# MicroMod-Artemis-ProcessorBoard.net
KiCad netlist of a schematic drawn in EAGLE
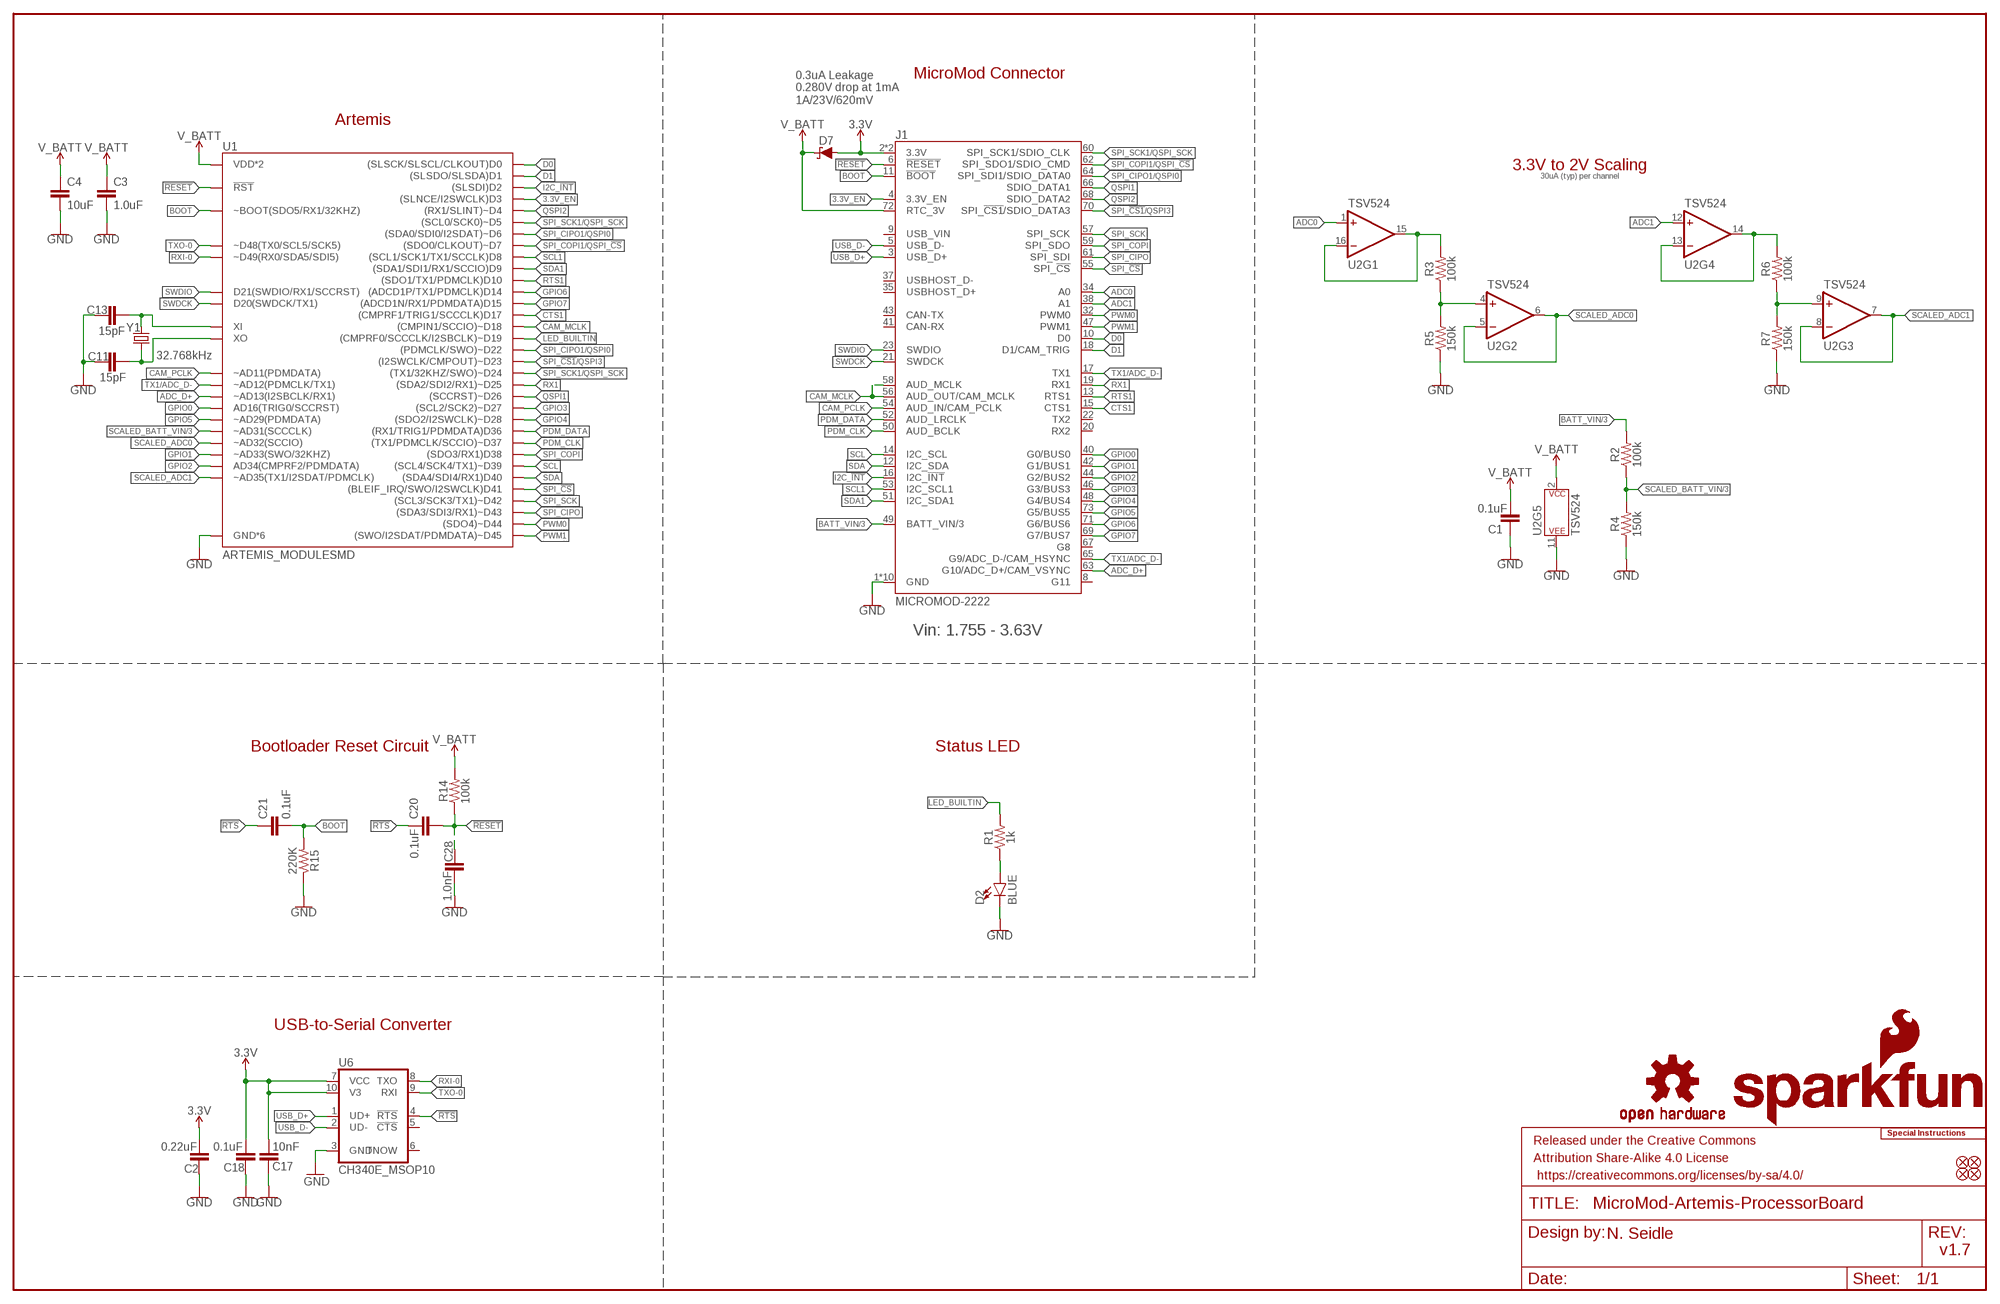
[diagram p0: schematic, sheet 1]

(export (version "E")
  (design (tool "Eeschema 10.0.6"))
  (components
    (comp (ref "C1")
      (value "0.1uF")
      (footprint "eagle-import:0402-TIGHT")
      (libsource (lib "eagle-import") (part "0.1UF-0402T-16V-10%"))
    )
    (comp (ref "C2")
      (value "0.22uF")
      (footprint "eagle-import:0402-TIGHT")
      (libsource (lib "eagle-import") (part "0.22UF-0402T-10V-10%"))
    )
    (comp (ref "C3")
      (value "1.0uF")
      (footprint "eagle-import:0402-TIGHT")
      (libsource (lib "eagle-import") (part "1.0UF-0402T-16V-10%"))
    )
    (comp (ref "C4")
      (value "10uF")
      (footprint "eagle-import:0603")
      (libsource (lib "eagle-import") (part "10UF-0603-6.3V-20%"))
    )
    (comp (ref "C11")
      (value "15pF")
      (footprint "eagle-import:0402-TIGHT")
      (libsource (lib "eagle-import") (part "15PF-0402T-50V-5%"))
    )
    (comp (ref "C13")
      (value "15pF")
      (footprint "eagle-import:0402-TIGHT")
      (libsource (lib "eagle-import") (part "15PF-0402T-50V-5%"))
    )
    (comp (ref "C17")
      (value "10nF")
      (footprint "eagle-import:0402-TIGHT")
      (libsource (lib "eagle-import") (part "10NF-0402T-25V-10%"))
    )
    (comp (ref "C18")
      (value "0.1uF")
      (footprint "eagle-import:0402-TIGHT")
      (libsource (lib "eagle-import") (part "0.1UF-0402T-16V-10%"))
    )
    (comp (ref "C20")
      (value "0.1uF")
      (footprint "eagle-import:0402-TIGHT")
      (libsource (lib "eagle-import") (part "0.1UF-0402T-16V-10%"))
    )
    (comp (ref "C21")
      (value "0.1uF")
      (footprint "eagle-import:0402-TIGHT")
      (libsource (lib "eagle-import") (part "0.1UF-0402T-16V-10%"))
    )
    (comp (ref "C28")
      (value "1.0nF")
      (footprint "eagle-import:0402-TIGHT")
      (libsource (lib "eagle-import") (part "1.0NF/1000PF-0402_TIGHT-50V-10%"))
    )
    (comp (ref "D2")
      (value "BLUE")
      (footprint "eagle-import:LED-0603")
      (libsource (lib "eagle-import") (part "LED-BLUE0603"))
    )
    (comp (ref "D7")
      (value "1A/23V/620mV")
      (footprint "eagle-import:SOD-323")
      (libsource (lib "eagle-import") (part "DIODE-SCHOTTKY-BAT20J"))
    )
    (comp (ref "FD1")
      (value "FIDUCIALUFIDUCIAL")
      (footprint "eagle-import:FIDUCIAL-MICRO")
      (libsource (lib "eagle-import") (part "FIDUCIALUFIDUCIAL"))
    )
    (comp (ref "FD2")
      (value "FIDUCIALUFIDUCIAL")
      (footprint "eagle-import:FIDUCIAL-MICRO")
      (libsource (lib "eagle-import") (part "FIDUCIALUFIDUCIAL"))
    )
    (comp (ref "FD3")
      (value "FIDUCIALUFIDUCIAL")
      (footprint "eagle-import:FIDUCIAL-MICRO")
      (libsource (lib "eagle-import") (part "FIDUCIALUFIDUCIAL"))
    )
    (comp (ref "FD4")
      (value "FIDUCIALUFIDUCIAL")
      (footprint "eagle-import:FIDUCIAL-MICRO")
      (libsource (lib "eagle-import") (part "FIDUCIALUFIDUCIAL"))
    )
    (comp (ref "FRAME1")
      (value "FRAME-LEDGER")
      (footprint "eagle-import:CREATIVE_COMMONS")
      (libsource (lib "eagle-import") (part "FRAME-LEDGER"))
    )
    (comp (ref "J1")
      (value "MICROMOD-2222")
      (footprint "eagle-import:M.2-CARD-E-22")
      (libsource (lib "eagle-import") (part "MICROMOD-2222"))
    )
    (comp (ref "LOGO1")
      (value "SFE_LOGO_NAME_FLAME.1_INCH")
      (footprint "eagle-import:SFE_LOGO_NAME_FLAME_.1")
      (libsource (lib "eagle-import") (part "SFE_LOGO_NAME_FLAME.1_INCH"))
    )
    (comp (ref "LOGO2")
      (value "SFE_LOGO_FLAME.1_INCH")
      (footprint "eagle-import:SFE_LOGO_FLAME_.1")
      (libsource (lib "eagle-import") (part "SFE_LOGO_FLAME.1_INCH"))
    )
    (comp (ref "LOGO3")
      (value "OSHW-LOGOMINI")
      (footprint "eagle-import:OSHW-LOGO-MINI")
      (libsource (lib "eagle-import") (part "OSHW-LOGOMINI"))
    )
    (comp (ref "LOGO4")
      (value "SPECIAL_INSTRUCTIONS-ORDERING")
      (footprint "eagle-import:ORDERING_INSTRUCTIONS")
      (libsource (lib "eagle-import") (part "SPECIAL_INSTRUCTIONS-ORDERING"))
    )
    (comp (ref "R1")
      (value "1k")
      (footprint "eagle-import:0402-TIGHT")
      (libsource (lib "eagle-import") (part "1KOHM-0402T-1/16W-1%"))
    )
    (comp (ref "R2")
      (value "100k")
      (footprint "eagle-import:0402-TIGHT")
      (libsource (lib "eagle-import") (part "100KOHM-0402T-1/16W-1%"))
    )
    (comp (ref "R3")
      (value "100k")
      (footprint "eagle-import:0402-TIGHT")
      (libsource (lib "eagle-import") (part "100KOHM-0402T-1/16W-1%"))
    )
    (comp (ref "R4")
      (value "150k")
      (footprint "eagle-import:0402-TIGHT")
      (libsource (lib "eagle-import") (part "150KOHM-0402T-1/16W-1%"))
    )
    (comp (ref "R5")
      (value "150k")
      (footprint "eagle-import:0402-TIGHT")
      (libsource (lib "eagle-import") (part "150KOHM-0402T-1/16W-1%"))
    )
    (comp (ref "R6")
      (value "100k")
      (footprint "eagle-import:0402-TIGHT")
      (libsource (lib "eagle-import") (part "100KOHM-0402T-1/16W-1%"))
    )
    (comp (ref "R7")
      (value "150k")
      (footprint "eagle-import:0402-TIGHT")
      (libsource (lib "eagle-import") (part "150KOHM-0402T-1/16W-1%"))
    )
    (comp (ref "R14")
      (value "100k")
      (footprint "eagle-import:0402-TIGHT")
      (libsource (lib "eagle-import") (part "100KOHM-0402T-1/16W-1%"))
    )
    (comp (ref "R15")
      (value "220K")
      (footprint "eagle-import:0402-TIGHT")
      (libsource (lib "eagle-import") (part "220KOHM-0402T-1/16W-1%"))
    )
    (comp (ref "U1")
      (value "ARTEMIS_MODULESMD")
      (footprint "eagle-import:ARTEMIS_FP")
      (libsource (lib "eagle-import") (part "ARTEMIS_MODULESMD"))
    )
    (comp (ref "U2")
      (value "TSV524")
      (footprint "eagle-import:QFN-16")
      (libsource (lib "eagle-import") (part "TSV524"))
    )
    (comp (ref "U6")
      (value "CH340E_MSOP10")
      (footprint "eagle-import:MSOP10")
      (libsource (lib "eagle-import") (part "CH340E_MSOP10"))
    )
    (comp (ref "Y1")
      (value "32.768kHz")
      (footprint "eagle-import:CRYSTAL-SMD-3.2X1.5MM")
      (libsource (lib "eagle-import") (part "CRYSTAL-32.768KHZSMD-3.2X1.5"))
    )
  )
  (nets
    (net (code "1") (name "/I2C_~{INT}") (class "Default")
      (node (ref "J1") (pin "16") (pinfunction "I2C_~{INT}_16") (pintype "bidirectional"))
      (node (ref "U1") (pin "D2") (pinfunction "(SLSDI)D2_D2") (pintype "bidirectional"))
    )
    (net (code "2") (name "/SPI_COPI1{slash}QSPI_~{CS}") (class "Default")
      (node (ref "J1") (pin "62") (pinfunction "SPI_SDO1/SDIO_CMD_62") (pintype "bidirectional"))
      (node (ref "U1") (pin "D7") (pinfunction "(SDO0/CLKOUT)~{D7}_D7") (pintype "bidirectional"))
    )
    (net (code "3") (name "/SPI_~{CS1}{slash}QSPI3") (class "Default")
      (node (ref "J1") (pin "70") (pinfunction "SPI_~{CS1}/SDIO_DATA3_70") (pintype "bidirectional"))
      (node (ref "U1") (pin "~D23") (pinfunction "(I2SWCLK/CMPOUT)~{D23}_~D23") (pintype "bidirectional"))
    )
    (net (code "4") (name "/SPI_~{CS}") (class "Default")
      (node (ref "J1") (pin "55") (pinfunction "SPI_~{CS}_55") (pintype "bidirectional"))
      (node (ref "U1") (pin "D41") (pinfunction "(BLEIF_IRQ/SWO/I2SWCLK)D41_D41") (pintype "bidirectional"))
    )
    (net (code "5") (name "/~{RESET}") (class "Default")
      (node (ref "C20") (pin "2") (pinfunction "2_2") (pintype "passive"))
      (node (ref "C28") (pin "1") (pinfunction "1_1") (pintype "passive"))
      (node (ref "J1") (pin "6") (pinfunction "~{RESET}_6") (pintype "bidirectional"))
      (node (ref "R14") (pin "1") (pinfunction "1_1") (pintype "passive"))
      (node (ref "U1") (pin "~RST") (pinfunction "~{RST}_~RST") (pintype "bidirectional"))
    )
    (net (code "6") (name "/~{RTS}") (class "Default")
      (node (ref "C20") (pin "1") (pinfunction "1_1") (pintype "passive"))
      (node (ref "C21") (pin "1") (pinfunction "1_1") (pintype "passive"))
      (node (ref "U6") (pin "4") (pinfunction "~{RTS}_4") (pintype "bidirectional"))
    )
    (net (code "7") (name "3.3V") (class "Default")
      (node (ref "C17") (pin "1") (pinfunction "1_1") (pintype "passive"))
      (node (ref "C18") (pin "1") (pinfunction "1_1") (pintype "passive"))
      (node (ref "C2") (pin "1") (pinfunction "1_1") (pintype "passive"))
      (node (ref "D7") (pin "A") (pinfunction "A_A") (pintype "passive"))
      (node (ref "J1") (pin "2") (pinfunction "3.3V_2") (pintype "bidirectional"))
      (node (ref "J1") (pin "74") (pinfunction "3.3V_74") (pintype "bidirectional"))
      (node (ref "U6") (pin "10") (pinfunction "V3_10") (pintype "bidirectional"))
      (node (ref "U6") (pin "7") (pinfunction "VCC_7") (pintype "bidirectional"))
    )
    (net (code "8") (name "3.3V_EN") (class "Default")
      (node (ref "J1") (pin "4") (pinfunction "3.3V_EN_4") (pintype "bidirectional"))
      (node (ref "U1") (pin "D3") (pinfunction "(SLNCE/I2SWCLK)D3_D3") (pintype "bidirectional"))
    )
    (net (code "9") (name "ADC0") (class "Default")
      (node (ref "J1") (pin "34") (pinfunction "A0_34") (pintype "bidirectional"))
      (node (ref "U2") (pin "1") (pinfunction "+IN_1") (pintype "input"))
    )
    (net (code "10") (name "ADC1") (class "Default")
      (node (ref "J1") (pin "38") (pinfunction "A1_38") (pintype "bidirectional"))
      (node (ref "U2") (pin "12") (pinfunction "+IN_12") (pintype "input"))
    )
    (net (code "11") (name "ADC_D+") (class "Default")
      (node (ref "J1") (pin "63") (pinfunction "G10/ADC_D+/CAM_VSYNC_63") (pintype "bidirectional"))
      (node (ref "U1") (pin "~AD13") (pinfunction "~{AD13(I2SBCLK/RX1})_~AD13") (pintype "bidirectional"))
    )
    (net (code "12") (name "BATT_VIN{slash}3") (class "Default")
      (node (ref "J1") (pin "49") (pinfunction "BATT_VIN/3_49") (pintype "bidirectional"))
      (node (ref "R2") (pin "2") (pinfunction "2_2") (pintype "passive"))
    )
    (net (code "13") (name "BOOT") (class "Default")
      (node (ref "C21") (pin "2") (pinfunction "2_2") (pintype "passive"))
      (node (ref "J1") (pin "11") (pinfunction "~{BOOT}_11") (pintype "bidirectional"))
      (node (ref "R15") (pin "2") (pinfunction "2_2") (pintype "passive"))
      (node (ref "U1") (pin "BOOT") (pinfunction "~{BOOT(SDO5/RX1/32KHZ})_BOOT") (pintype "bidirectional"))
    )
    (net (code "14") (name "CAM_MCLK") (class "Default")
      (node (ref "J1") (pin "56") (pinfunction "AUD_OUT/CAM_MCLK_56") (pintype "bidirectional"))
      (node (ref "J1") (pin "58") (pinfunction "AUD_MCLK_58") (pintype "bidirectional"))
      (node (ref "U1") (pin "~D18") (pinfunction "(CMPIN1/SCCIO)~{D18}_~D18") (pintype "bidirectional"))
    )
    (net (code "15") (name "CAM_PCLK") (class "Default")
      (node (ref "J1") (pin "54") (pinfunction "AUD_IN/CAM_PCLK_54") (pintype "bidirectional"))
      (node (ref "U1") (pin "~AD11") (pinfunction "~{AD11(PDMDATA})_~AD11") (pintype "bidirectional"))
    )
    (net (code "16") (name "CTS1") (class "Default")
      (node (ref "J1") (pin "15") (pinfunction "CTS1_15") (pintype "bidirectional"))
      (node (ref "U1") (pin "D17") (pinfunction "(CMPRF1/TRIG1/SCCCLK)D17_D17") (pintype "bidirectional"))
    )
    (net (code "17") (name "D0") (class "Default")
      (node (ref "J1") (pin "10") (pinfunction "D0_10") (pintype "bidirectional"))
      (node (ref "U1") (pin "D0") (pinfunction "(SLSCK/SLSCL/CLKOUT)D0_D0") (pintype "bidirectional"))
    )
    (net (code "18") (name "D1") (class "Default")
      (node (ref "J1") (pin "18") (pinfunction "D1/CAM_TRIG_18") (pintype "bidirectional"))
      (node (ref "U1") (pin "D1") (pinfunction "(SLSDO/SLSDA)D1_D1") (pintype "bidirectional"))
    )
    (net (code "19") (name "GND") (class "Default")
      (node (ref "C1") (pin "2") (pinfunction "2_2") (pintype "passive"))
      (node (ref "C11") (pin "1") (pinfunction "1_1") (pintype "passive"))
      (node (ref "C13") (pin "1") (pinfunction "1_1") (pintype "passive"))
      (node (ref "C17") (pin "2") (pinfunction "2_2") (pintype "passive"))
      (node (ref "C18") (pin "2") (pinfunction "2_2") (pintype "passive"))
      (node (ref "C2") (pin "2") (pinfunction "2_2") (pintype "passive"))
      (node (ref "C28") (pin "2") (pinfunction "2_2") (pintype "passive"))
      (node (ref "C3") (pin "2") (pinfunction "2_2") (pintype "passive"))
      (node (ref "C4") (pin "2") (pinfunction "2_2") (pintype "passive"))
      (node (ref "D2") (pin "C") (pinfunction "C_C") (pintype "passive"))
      (node (ref "J1") (pin "1") (pinfunction "GND_1") (pintype "bidirectional"))
      (node (ref "J1") (pin "33") (pinfunction "GND_33") (pintype "bidirectional"))
      (node (ref "J1") (pin "36") (pinfunction "GND_36") (pintype "bidirectional"))
      (node (ref "J1") (pin "39") (pinfunction "GND_39") (pintype "bidirectional"))
      (node (ref "J1") (pin "45") (pinfunction "GND_45") (pintype "bidirectional"))
      (node (ref "J1") (pin "7") (pinfunction "GND_7") (pintype "bidirectional"))
      (node (ref "J1") (pin "75") (pinfunction "GND_75") (pintype "bidirectional"))
      (node (ref "J1") (pin "GND1") (pinfunction "GND_GND1") (pintype "bidirectional"))
      (node (ref "J1") (pin "GND2") (pinfunction "GND_GND2") (pintype "bidirectional"))
      (node (ref "J1") (pin "GND3") (pinfunction "GND_GND3") (pintype "bidirectional"))
      (node (ref "R15") (pin "1") (pinfunction "1_1") (pintype "passive"))
      (node (ref "R4") (pin "1") (pinfunction "1_1") (pintype "passive"))
      (node (ref "R5") (pin "1") (pinfunction "1_1") (pintype "passive"))
      (node (ref "R7") (pin "1") (pinfunction "1_1") (pintype "passive"))
      (node (ref "U1") (pin "GND@1") (pinfunction "GND*6_GND@1") (pintype "bidirectional"))
      (node (ref "U1") (pin "GND@22") (pinfunction "GND*6_GND@22") (pintype "bidirectional"))
      (node (ref "U1") (pin "GND@38") (pinfunction "GND*6_GND@38") (pintype "bidirectional"))
      (node (ref "U1") (pin "GND@39") (pinfunction "GND*6_GND@39") (pintype "bidirectional"))
      (node (ref "U1") (pin "GND@47") (pinfunction "GND*6_GND@47") (pintype "bidirectional"))
      (node (ref "U1") (pin "GND@59") (pinfunction "GND*6_GND@59") (pintype "bidirectional"))
      (node (ref "U2") (pin "11") (pinfunction "V-_11") (pintype "bidirectional"))
      (node (ref "U6") (pin "3") (pinfunction "GND_3") (pintype "bidirectional"))
    )
    (net (code "20") (name "GPIO0") (class "Default")
      (node (ref "J1") (pin "40") (pinfunction "G0/BUS0_40") (pintype "bidirectional"))
      (node (ref "U1") (pin "AD16") (pinfunction "AD16(TRIG0/SCCRST)_AD16") (pintype "bidirectional"))
    )
    (net (code "21") (name "GPIO1") (class "Default")
      (node (ref "J1") (pin "42") (pinfunction "G1/BUS1_42") (pintype "bidirectional"))
      (node (ref "U1") (pin "~AD33/SWO") (pinfunction "~{AD33(SWO/32KHZ})_~AD33/SWO") (pintype "bidirectional"))
    )
    (net (code "22") (name "GPIO2") (class "Default")
      (node (ref "J1") (pin "44") (pinfunction "G2/BUS2_44") (pintype "bidirectional"))
      (node (ref "U1") (pin "AD34") (pinfunction "AD34(CMPRF2/PDMDATA)_AD34") (pintype "bidirectional"))
    )
    (net (code "23") (name "GPIO3") (class "Default")
      (node (ref "J1") (pin "46") (pinfunction "G3/BUS3_46") (pintype "bidirectional"))
      (node (ref "U1") (pin "~D27") (pinfunction "(SCL2/SCK2)~{D27}_~D27") (pintype "bidirectional"))
    )
    (net (code "24") (name "GPIO4") (class "Default")
      (node (ref "J1") (pin "48") (pinfunction "G4/BUS4_48") (pintype "bidirectional"))
      (node (ref "U1") (pin "~D28") (pinfunction "(SDO2/I2SWCLK)~{D28}_~D28") (pintype "bidirectional"))
    )
    (net (code "25") (name "GPIO5") (class "Default")
      (node (ref "J1") (pin "73") (pinfunction "G5/BUS5_73") (pintype "bidirectional"))
      (node (ref "U1") (pin "~AD29") (pinfunction "~{AD29(PDMDATA})_~AD29") (pintype "bidirectional"))
    )
    (net (code "26") (name "GPIO6") (class "Default")
      (node (ref "J1") (pin "71") (pinfunction "G6/BUS6_71") (pintype "bidirectional"))
      (node (ref "U1") (pin "D14") (pinfunction "(ADCD1P/TX1/PDMCLK)D14_D14") (pintype "bidirectional"))
    )
    (net (code "27") (name "GPIO7") (class "Default")
      (node (ref "J1") (pin "69") (pinfunction "G7/BUS7_69") (pintype "bidirectional"))
      (node (ref "U1") (pin "D15") (pinfunction "(ADCD1N/RX1/PDMDATA)D15_D15") (pintype "bidirectional"))
    )
    (net (code "28") (name "LED_BUILTIN") (class "Default")
      (node (ref "R1") (pin "2") (pinfunction "2_2") (pintype "passive"))
      (node (ref "U1") (pin "~D19") (pinfunction "(CMPRF0/SCCCLK/I2SBCLK)~{D19}_~D19") (pintype "bidirectional"))
    )
    (net (code "29") (name "Net-(D2-PadA)") (class "Default")
      (node (ref "D2") (pin "A") (pinfunction "A_A") (pintype "passive"))
      (node (ref "R1") (pin "1") (pinfunction "1_1") (pintype "passive"))
    )
    (net (code "30") (name "Net-(U2A--IN)") (class "Default")
      (node (ref "R3") (pin "2") (pinfunction "2_2") (pintype "passive"))
      (node (ref "U2") (pin "15") (pinfunction "OUT_15") (pintype "output"))
      (node (ref "U2") (pin "16") (pinfunction "-IN_16") (pintype "input"))
    )
    (net (code "31") (name "Net-(U2B-+IN)") (class "Default")
      (node (ref "R3") (pin "1") (pinfunction "1_1") (pintype "passive"))
      (node (ref "R5") (pin "2") (pinfunction "2_2") (pintype "passive"))
      (node (ref "U2") (pin "4") (pinfunction "+IN_4") (pintype "input"))
    )
    (net (code "32") (name "Net-(U2C-+IN)") (class "Default")
      (node (ref "R6") (pin "1") (pinfunction "1_1") (pintype "passive"))
      (node (ref "R7") (pin "2") (pinfunction "2_2") (pintype "passive"))
      (node (ref "U2") (pin "9") (pinfunction "+IN_9") (pintype "input"))
    )
    (net (code "33") (name "Net-(U2D--IN)") (class "Default")
      (node (ref "R6") (pin "2") (pinfunction "2_2") (pintype "passive"))
      (node (ref "U2") (pin "13") (pinfunction "-IN_13") (pintype "input"))
      (node (ref "U2") (pin "14") (pinfunction "OUT_14") (pintype "output"))
    )
    (net (code "34") (name "Net-(Y1-1)") (class "Default")
      (node (ref "C13") (pin "2") (pinfunction "2_2") (pintype "passive"))
      (node (ref "U1") (pin "XI") (pinfunction "XI_XI") (pintype "bidirectional"))
      (node (ref "Y1") (pin "P$1") (pinfunction "1_P$1") (pintype "passive"))
    )
    (net (code "35") (name "Net-(Y1-2)") (class "Default")
      (node (ref "C11") (pin "2") (pinfunction "2_2") (pintype "passive"))
      (node (ref "U1") (pin "XO") (pinfunction "XO_XO") (pintype "bidirectional"))
      (node (ref "Y1") (pin "P$2") (pinfunction "2_P$2") (pintype "passive"))
    )
    (net (code "36") (name "PDM_CLK") (class "Default")
      (node (ref "J1") (pin "50") (pinfunction "AUD_BCLK_50") (pintype "bidirectional"))
      (node (ref "U1") (pin "~D37") (pinfunction "(TX1/PDMCLK/SCCIO)~{D37}_~D37") (pintype "bidirectional"))
    )
    (net (code "37") (name "PDM_DATA") (class "Default")
      (node (ref "J1") (pin "52") (pinfunction "AUD_LRCLK_52") (pintype "bidirectional"))
      (node (ref "U1") (pin "D36") (pinfunction "(RX1/TRIG1/PDMDATA)D36_D36") (pintype "bidirectional"))
    )
    (net (code "38") (name "PWM0") (class "Default")
      (node (ref "J1") (pin "32") (pinfunction "PWM0_32") (pintype "bidirectional"))
      (node (ref "U1") (pin "~D44") (pinfunction "(SDO4)~{D44}_~D44") (pintype "bidirectional"))
    )
    (net (code "39") (name "PWM1") (class "Default")
      (node (ref "J1") (pin "47") (pinfunction "PWM1_47") (pintype "bidirectional"))
      (node (ref "U1") (pin "~D45") (pinfunction "(SWO/I2SDAT/PDMDATA)~{D45}_~D45") (pintype "bidirectional"))
    )
    (net (code "40") (name "QSPI1") (class "Default")
      (node (ref "J1") (pin "66") (pinfunction "SDIO_DATA1_66") (pintype "bidirectional"))
      (node (ref "U1") (pin "~D26") (pinfunction "(SCCRST)~{D26}_~D26") (pintype "bidirectional"))
    )
    (net (code "41") (name "QSPI2") (class "Default")
      (node (ref "J1") (pin "68") (pinfunction "SDIO_DATA2_68") (pintype "bidirectional"))
      (node (ref "U1") (pin "~D4") (pinfunction "(RX1/SLINT)~{D4}_~D4") (pintype "bidirectional"))
    )
    (net (code "42") (name "RTS1") (class "Default")
      (node (ref "J1") (pin "13") (pinfunction "RTS1_13") (pintype "bidirectional"))
      (node (ref "U1") (pin "D10") (pinfunction "(SDO1/TX1/PDMCLK)D10_D10") (pintype "bidirectional"))
    )
    (net (code "43") (name "RX1") (class "Default")
      (node (ref "J1") (pin "19") (pinfunction "RX1_19") (pintype "bidirectional"))
      (node (ref "U1") (pin "~D25") (pinfunction "(SDA2/SDI2/RX1)~{D25}_~D25") (pintype "bidirectional"))
    )
    (net (code "44") (name "RXI-0") (class "Default")
      (node (ref "U1") (pin "RXI-0") (pinfunction "~{D49(RX0/SDA5/SDI5})_RXI-0") (pintype "bidirectional"))
      (node (ref "U6") (pin "8") (pinfunction "TXO_8") (pintype "bidirectional"))
    )
    (net (code "45") (name "SCALED_ADC0") (class "Default")
      (node (ref "U1") (pin "~AD32") (pinfunction "~{AD32(SCCIO})_~AD32") (pintype "bidirectional"))
      (node (ref "U2") (pin "5") (pinfunction "-IN_5") (pintype "input"))
      (node (ref "U2") (pin "6") (pinfunction "OUT_6") (pintype "output"))
    )
    (net (code "46") (name "SCALED_ADC1") (class "Default")
      (node (ref "U1") (pin "~AD35") (pinfunction "~{AD35(TX1/I2SDAT/PDMCLK})_~AD35") (pintype "bidirectional"))
      (node (ref "U2") (pin "7") (pinfunction "OUT_7") (pintype "output"))
      (node (ref "U2") (pin "8") (pinfunction "-IN_8") (pintype "input"))
    )
    (net (code "47") (name "SCALED_BATT_VIN{slash}3") (class "Default")
      (node (ref "R2") (pin "1") (pinfunction "1_1") (pintype "passive"))
      (node (ref "R4") (pin "2") (pinfunction "2_2") (pintype "passive"))
      (node (ref "U1") (pin "~AD31") (pinfunction "~{AD31(SCCCLK})_~AD31") (pintype "bidirectional"))
    )
    (net (code "48") (name "SCL") (class "Default")
      (node (ref "J1") (pin "14") (pinfunction "I2C_SCL_14") (pintype "bidirectional"))
      (node (ref "U1") (pin "~D39") (pinfunction "(SCL4/SCK4/TX1)~{D39}_~D39") (pintype "bidirectional"))
    )
    (net (code "49") (name "SCL1") (class "Default")
      (node (ref "J1") (pin "53") (pinfunction "I2C_SCL1_53") (pintype "bidirectional"))
      (node (ref "U1") (pin "D8") (pinfunction "(SCL1/SCK1/TX1/SCCLK)D8_D8") (pintype "bidirectional"))
    )
    (net (code "50") (name "SDA") (class "Default")
      (node (ref "J1") (pin "12") (pinfunction "I2C_SDA_12") (pintype "bidirectional"))
      (node (ref "U1") (pin "D40") (pinfunction "(SDA4/SDI4/RX1)D40_D40") (pintype "bidirectional"))
    )
    (net (code "51") (name "SDA1") (class "Default")
      (node (ref "J1") (pin "51") (pinfunction "I2C_SDA1_51") (pintype "bidirectional"))
      (node (ref "U1") (pin "D9") (pinfunction "(SDA1/SDI1/RX1/SCCIO)D9_D9") (pintype "bidirectional"))
    )
    (net (code "52") (name "SPI_CIPO") (class "Default")
      (node (ref "J1") (pin "61") (pinfunction "SPI_SDI_61") (pintype "bidirectional"))
      (node (ref "U1") (pin "~D43") (pinfunction "(SDA3/SDI3/RX1)~{D43}_~D43") (pintype "bidirectional"))
    )
    (net (code "53") (name "SPI_CIPO1{slash}QSPI0") (class "Default")
      (node (ref "J1") (pin "64") (pinfunction "SPI_SDI1/SDIO_DATA0_64") (pintype "bidirectional"))
      (node (ref "U1") (pin "~D22") (pinfunction "(PDMCLK/SWO)~{D22}_~D22") (pintype "bidirectional"))
      (node (ref "U1") (pin "~D6") (pinfunction "(SDA0/SDI0/I2SDAT)~{D6}_~D6") (pintype "bidirectional"))
    )
    (net (code "54") (name "SPI_COPI") (class "Default")
      (node (ref "J1") (pin "59") (pinfunction "SPI_SDO_59") (pintype "bidirectional"))
      (node (ref "U1") (pin "D38") (pinfunction "(SDO3/RX1)D38_D38") (pintype "bidirectional"))
    )
    (net (code "55") (name "SPI_SCK") (class "Default")
      (node (ref "J1") (pin "57") (pinfunction "SPI_SCK_57") (pintype "bidirectional"))
      (node (ref "U1") (pin "~D42") (pinfunction "(SCL3/SCK3/TX1)~{D42}_~D42") (pintype "bidirectional"))
    )
    (net (code "56") (name "SPI_SCK1{slash}QSPI_SCK") (class "Default")
      (node (ref "J1") (pin "60") (pinfunction "SPI_SCK1/SDIO_CLK_60") (pintype "bidirectional"))
      (node (ref "U1") (pin "~D24") (pinfunction "(TX1/32KHZ/SWO)~{D24}_~D24") (pintype "bidirectional"))
      (node (ref "U1") (pin "~D5") (pinfunction "(SCL0/SCK0)~{D5}_~D5") (pintype "bidirectional"))
    )
    (net (code "57") (name "SWDCK") (class "Default")
      (node (ref "J1") (pin "21") (pinfunction "SWDCK_21") (pintype "bidirectional"))
      (node (ref "U1") (pin "SWDCK") (pinfunction "D20(SWDCK/TX1)_SWDCK") (pintype "bidirectional"))
    )
    (net (code "58") (name "SWDIO") (class "Default")
      (node (ref "J1") (pin "23") (pinfunction "SWDIO_23") (pintype "bidirectional"))
      (node (ref "U1") (pin "SWDIO") (pinfunction "D21(SWDIO/RX1/SCCRST)_SWDIO") (pintype "bidirectional"))
    )
    (net (code "59") (name "TX1{slash}ADC_D-") (class "Default")
      (node (ref "J1") (pin "17") (pinfunction "TX1_17") (pintype "bidirectional"))
      (node (ref "J1") (pin "65") (pinfunction "G9/ADC_D-/CAM_HSYNC_65") (pintype "bidirectional"))
      (node (ref "U1") (pin "~AD12") (pinfunction "~{AD12(PDMCLK/TX1})_~AD12") (pintype "bidirectional"))
    )
    (net (code "60") (name "TXO-0") (class "Default")
      (node (ref "U1") (pin "TXO-0") (pinfunction "~{D48(TX0/SCL5/SCK5})_TXO-0") (pintype "bidirectional"))
      (node (ref "U6") (pin "9") (pinfunction "RXI_9") (pintype "bidirectional"))
    )
    (net (code "61") (name "USB_D+") (class "Default")
      (node (ref "J1") (pin "3") (pinfunction "USB_D+_3") (pintype "bidirectional"))
      (node (ref "U6") (pin "1") (pinfunction "UD+_1") (pintype "bidirectional"))
    )
    (net (code "62") (name "USB_D-") (class "Default")
      (node (ref "J1") (pin "5") (pinfunction "USB_D-_5") (pintype "bidirectional"))
      (node (ref "U6") (pin "2") (pinfunction "UD-_2") (pintype "bidirectional"))
    )
    (net (code "63") (name "V_BATT") (class "Default")
      (node (ref "C1") (pin "1") (pinfunction "1_1") (pintype "passive"))
      (node (ref "C3") (pin "1") (pinfunction "1_1") (pintype "passive"))
      (node (ref "C4") (pin "1") (pinfunction "1_1") (pintype "passive"))
      (node (ref "D7") (pin "C") (pinfunction "C_C") (pintype "passive"))
      (node (ref "J1") (pin "72") (pinfunction "RTC_3V_72") (pintype "bidirectional"))
      (node (ref "R14") (pin "2") (pinfunction "2_2") (pintype "passive"))
      (node (ref "U1") (pin "VDD@36") (pinfunction "VDD*2_VDD@36") (pintype "bidirectional"))
      (node (ref "U1") (pin "VDD@37") (pinfunction "VDD*2_VDD@37") (pintype "bidirectional"))
      (node (ref "U2") (pin "2") (pinfunction "V+_2") (pintype "bidirectional"))
    )
    (net (code "64") (name "unconnected-(J1-CAN-RX-Pad41)") (class "Default")
      (node (ref "J1") (pin "41") (pinfunction "CAN-RX_41") (pintype "bidirectional"))
    )
    (net (code "65") (name "unconnected-(J1-CAN-TX-Pad43)") (class "Default")
      (node (ref "J1") (pin "43") (pinfunction "CAN-TX_43") (pintype "bidirectional"))
    )
    (net (code "66") (name "unconnected-(J1-G8-Pad67)") (class "Default")
      (node (ref "J1") (pin "67") (pinfunction "G8_67") (pintype "bidirectional"))
    )
    (net (code "67") (name "unconnected-(J1-G11-Pad8)") (class "Default")
      (node (ref "J1") (pin "8") (pinfunction "G11_8") (pintype "bidirectional"))
    )
    (net (code "68") (name "unconnected-(J1-RX2-Pad20)") (class "Default")
      (node (ref "J1") (pin "20") (pinfunction "RX2_20") (pintype "bidirectional"))
    )
    (net (code "69") (name "unconnected-(J1-TX2-Pad22)") (class "Default")
      (node (ref "J1") (pin "22") (pinfunction "TX2_22") (pintype "bidirectional"))
    )
    (net (code "70") (name "unconnected-(J1-USBHOST_D+-Pad35)") (class "Default")
      (node (ref "J1") (pin "35") (pinfunction "USBHOST_D+_35") (pintype "bidirectional"))
    )
    (net (code "71") (name "unconnected-(J1-USBHOST_D--Pad37)") (class "Default")
      (node (ref "J1") (pin "37") (pinfunction "USBHOST_D-_37") (pintype "bidirectional"))
    )
    (net (code "72") (name "unconnected-(J1-USB_VIN-Pad9)") (class "Default")
      (node (ref "J1") (pin "9") (pinfunction "USB_VIN_9") (pintype "bidirectional"))
    )
    (net (code "73") (name "unconnected-(U6-TNOW-Pad6)") (class "Default")
      (node (ref "U6") (pin "6") (pinfunction "TNOW_6") (pintype "bidirectional"))
    )
    (net (code "74") (name "unconnected-(U6-~{CTS}-Pad5)") (class "Default")
      (node (ref "U6") (pin "5") (pinfunction "~{CTS}_5") (pintype "bidirectional"))
    )
  )
)
